# led_board.net
KiCad netlist of a schematic drawn in EasyEDA Pro
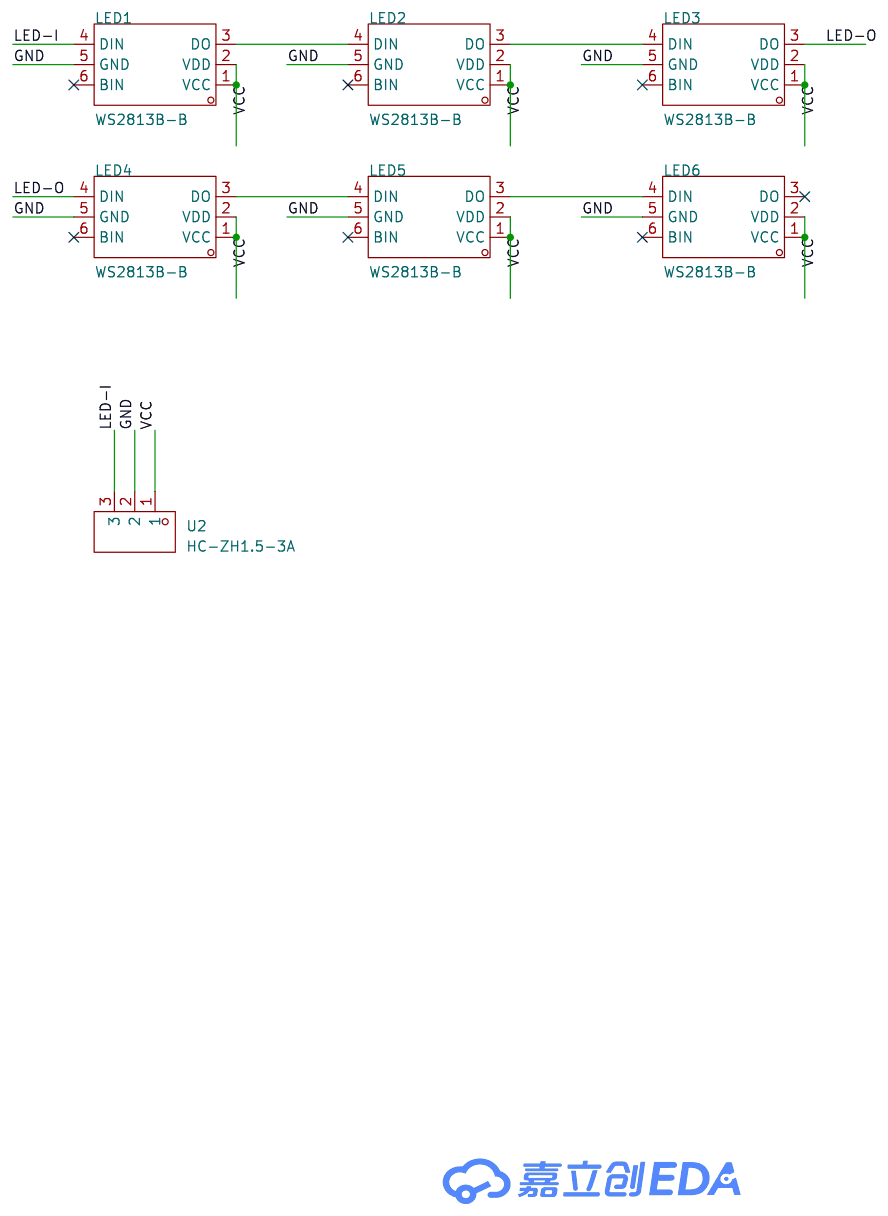
[diagram p0: schematic sheet]

(export (version "E")
  (design (tool "Eeschema 10.0.6"))
  (components
    (comp (ref "LED1")
      (value "WS2813B-B")
      (footprint "easyedapro:LED-SMD_6P-L5.0-W5.0-TL")
      (description "照明颜色:RGB三色;")
      (fields (field (name "Manufacturer") "worldsemi"))
      (libsource (lib "easyedapro") (part "WS2813B-B"))
    )
    (comp (ref "LED2")
      (value "WS2813B-B")
      (footprint "easyedapro:LED-SMD_6P-L5.0-W5.0-TL")
      (description "照明颜色:RGB三色;")
      (fields (field (name "Manufacturer") "worldsemi"))
      (libsource (lib "easyedapro") (part "WS2813B-B"))
    )
    (comp (ref "LED3")
      (value "WS2813B-B")
      (footprint "easyedapro:LED-SMD_6P-L5.0-W5.0-TL")
      (description "照明颜色:RGB三色;")
      (fields (field (name "Manufacturer") "worldsemi"))
      (libsource (lib "easyedapro") (part "WS2813B-B"))
    )
    (comp (ref "LED4")
      (value "WS2813B-B")
      (footprint "easyedapro:LED-SMD_6P-L5.0-W5.0-TL")
      (description "照明颜色:RGB三色;")
      (fields (field (name "Manufacturer") "worldsemi"))
      (libsource (lib "easyedapro") (part "WS2813B-B"))
    )
    (comp (ref "LED5")
      (value "WS2813B-B")
      (footprint "easyedapro:LED-SMD_6P-L5.0-W5.0-TL")
      (description "照明颜色:RGB三色;")
      (fields (field (name "Manufacturer") "worldsemi"))
      (libsource (lib "easyedapro") (part "WS2813B-B"))
    )
    (comp (ref "LED6")
      (value "WS2813B-B")
      (footprint "easyedapro:LED-SMD_6P-L5.0-W5.0-TL")
      (description "照明颜色:RGB三色;")
      (fields (field (name "Manufacturer") "worldsemi"))
      (libsource (lib "easyedapro") (part "WS2813B-B"))
    )
    (comp (ref "U2")
      (value "HC-ZH1.5-3A")
      (fields (field (name "Manufacturer") "HCTL(华灿天禄)"))
      (libsource (lib "easyedapro") (part "XY-XH2.54-3A21"))
    )
  )
  (nets
    (net (code "1") (name "/GND") (class "Default")
      (node (ref "LED1") (pin "5") (pinfunction "GND_5") (pintype "input"))
      (node (ref "LED2") (pin "5") (pinfunction "GND_5") (pintype "input"))
      (node (ref "LED3") (pin "5") (pinfunction "GND_5") (pintype "input"))
      (node (ref "LED4") (pin "5") (pinfunction "GND_5") (pintype "input"))
      (node (ref "LED5") (pin "5") (pinfunction "GND_5") (pintype "input"))
      (node (ref "LED6") (pin "5") (pinfunction "GND_5") (pintype "input"))
      (node (ref "U2") (pin "2") (pinfunction "2_2") (pintype "unspecified"))
    )
    (net (code "2") (name "/LED-I") (class "Default")
      (node (ref "LED1") (pin "4") (pinfunction "DIN_4") (pintype "input"))
      (node (ref "U2") (pin "3") (pinfunction "3_3") (pintype "unspecified"))
    )
    (net (code "3") (name "/LED-O") (class "Default")
      (node (ref "LED3") (pin "3") (pinfunction "DO_3") (pintype "input"))
      (node (ref "LED4") (pin "4") (pinfunction "DIN_4") (pintype "input"))
    )
    (net (code "4") (name "/VCC") (class "Default")
      (node (ref "LED1") (pin "1") (pinfunction "VCC_1") (pintype "input"))
      (node (ref "LED1") (pin "2") (pinfunction "VDD_2") (pintype "input"))
      (node (ref "LED2") (pin "1") (pinfunction "VCC_1") (pintype "input"))
      (node (ref "LED2") (pin "2") (pinfunction "VDD_2") (pintype "input"))
      (node (ref "LED3") (pin "1") (pinfunction "VCC_1") (pintype "input"))
      (node (ref "LED3") (pin "2") (pinfunction "VDD_2") (pintype "input"))
      (node (ref "LED4") (pin "1") (pinfunction "VCC_1") (pintype "input"))
      (node (ref "LED4") (pin "2") (pinfunction "VDD_2") (pintype "input"))
      (node (ref "LED5") (pin "1") (pinfunction "VCC_1") (pintype "input"))
      (node (ref "LED5") (pin "2") (pinfunction "VDD_2") (pintype "input"))
      (node (ref "LED6") (pin "1") (pinfunction "VCC_1") (pintype "input"))
      (node (ref "LED6") (pin "2") (pinfunction "VDD_2") (pintype "input"))
      (node (ref "U2") (pin "1") (pinfunction "1_1") (pintype "unspecified"))
    )
    (net (code "5") (name "Net-(LED1-DO)") (class "Default")
      (node (ref "LED1") (pin "3") (pinfunction "DO_3") (pintype "input"))
      (node (ref "LED2") (pin "4") (pinfunction "DIN_4") (pintype "input"))
    )
    (net (code "6") (name "Net-(LED2-DO)") (class "Default")
      (node (ref "LED2") (pin "3") (pinfunction "DO_3") (pintype "input"))
      (node (ref "LED3") (pin "4") (pinfunction "DIN_4") (pintype "input"))
    )
    (net (code "7") (name "Net-(LED4-DO)") (class "Default")
      (node (ref "LED4") (pin "3") (pinfunction "DO_3") (pintype "input"))
      (node (ref "LED5") (pin "4") (pinfunction "DIN_4") (pintype "input"))
    )
    (net (code "8") (name "Net-(LED5-DO)") (class "Default")
      (node (ref "LED5") (pin "3") (pinfunction "DO_3") (pintype "input"))
      (node (ref "LED6") (pin "4") (pinfunction "DIN_4") (pintype "input"))
    )
    (net (code "9") (name "unconnected-(LED1-BIN-Pad6)") (class "Default")
      (node (ref "LED1") (pin "6") (pinfunction "BIN_6") (pintype "input+no_connect"))
    )
    (net (code "10") (name "unconnected-(LED2-BIN-Pad6)") (class "Default")
      (node (ref "LED2") (pin "6") (pinfunction "BIN_6") (pintype "input+no_connect"))
    )
    (net (code "11") (name "unconnected-(LED3-BIN-Pad6)") (class "Default")
      (node (ref "LED3") (pin "6") (pinfunction "BIN_6") (pintype "input+no_connect"))
    )
    (net (code "12") (name "unconnected-(LED4-BIN-Pad6)") (class "Default")
      (node (ref "LED4") (pin "6") (pinfunction "BIN_6") (pintype "input+no_connect"))
    )
    (net (code "13") (name "unconnected-(LED5-BIN-Pad6)") (class "Default")
      (node (ref "LED5") (pin "6") (pinfunction "BIN_6") (pintype "input+no_connect"))
    )
    (net (code "14") (name "unconnected-(LED6-BIN-Pad6)") (class "Default")
      (node (ref "LED6") (pin "6") (pinfunction "BIN_6") (pintype "input+no_connect"))
    )
    (net (code "15") (name "unconnected-(LED6-DO-Pad3)") (class "Default")
      (node (ref "LED6") (pin "3") (pinfunction "DO_3") (pintype "input+no_connect"))
    )
  )
)
